# kegtroller_v1.net
KiCad netlist of a schematic drawn in EAGLE
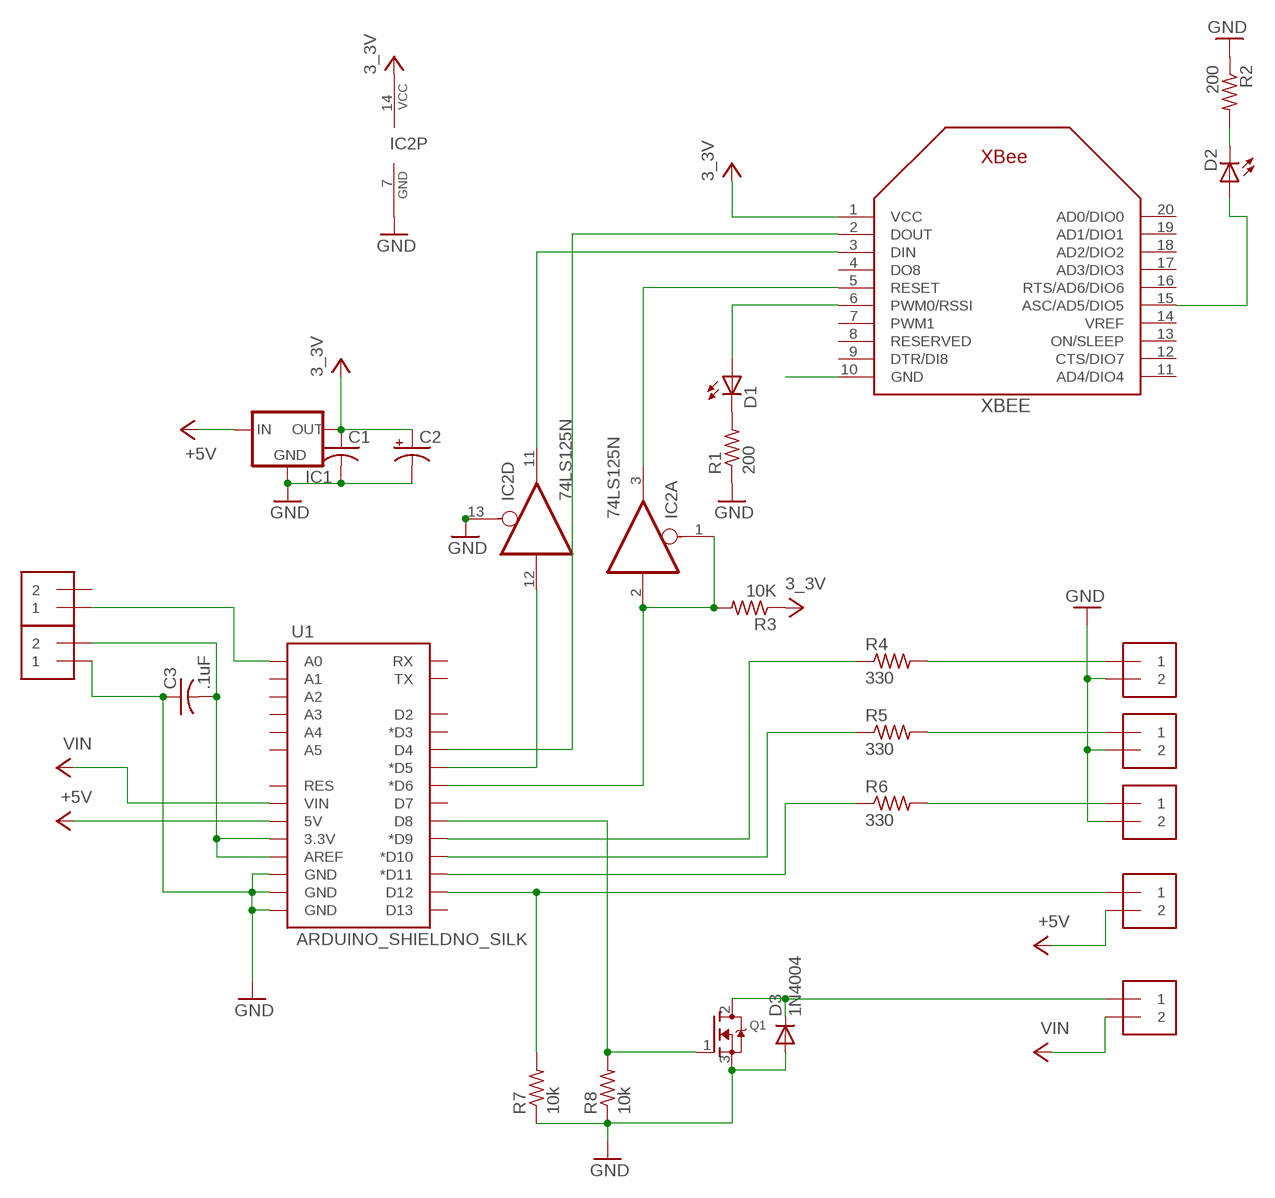
[diagram p0: schematic, sheet 1]

(export (version "E")
  (design (tool "Eeschema 10.0.6"))
  (components
    (comp (ref "C1")
      (value "C-US025-025X050")
      (footprint "eagle-import:C025-025X050")
      (libsource (lib "eagle-import") (part "rcl-ez_C-US025-025X050"))
    )
    (comp (ref "C2")
      (value "CPOL-USE2.5-5")
      (footprint "eagle-import:E2,5-5")
      (libsource (lib "eagle-import") (part "CPOL-USE2.5-5"))
    )
    (comp (ref "C3")
      (value ".1uF")
      (footprint "eagle-import:C025-025X050")
      (libsource (lib "eagle-import") (part "C-US025-025X050"))
    )
    (comp (ref "D1")
      (value "LED3MM")
      (footprint "eagle-import:LED3MM")
      (libsource (lib "eagle-import") (part "LED3MM"))
    )
    (comp (ref "D2")
      (value "LED3MM")
      (footprint "eagle-import:LED3MM")
      (libsource (lib "eagle-import") (part "LED3MM"))
    )
    (comp (ref "D3")
      (value "1N4004")
      (footprint "eagle-import:DO41-10")
      (libsource (lib "eagle-import") (part "1N4004"))
    )
    (comp (ref "IC1")
      (value "MC1700")
      (footprint "eagle-import:TO92")
      (libsource (lib "eagle-import") (part "MC1700"))
    )
    (comp (ref "IC2")
      (value "74LS125N")
      (footprint "eagle-import:DIL14")
      (libsource (lib "eagle-import") (part "74125NLS"))
    )
    (comp (ref "J1")
      (value "1X2-3.5MM")
      (footprint "eagle-import:1X2-3.5MM")
      (libsource (lib "eagle-import") (part "1X2-3.5MM"))
    )
    (comp (ref "J2")
      (value "1X2-3.5MM")
      (footprint "eagle-import:1X2-3.5MM")
      (libsource (lib "eagle-import") (part "1X2-3.5MM"))
    )
    (comp (ref "J3")
      (value "1X2-3.5MM")
      (footprint "eagle-import:1X2-3.5MM")
      (libsource (lib "eagle-import") (part "1X2-3.5MM"))
    )
    (comp (ref "J4")
      (value "1X2-3.5MM")
      (footprint "eagle-import:1X2-3.5MM")
      (libsource (lib "eagle-import") (part "1X2-3.5MM"))
    )
    (comp (ref "J5")
      (value "1X2-3.5MM")
      (footprint "eagle-import:1X2-3.5MM")
      (libsource (lib "eagle-import") (part "1X2-3.5MM"))
    )
    (comp (ref "J6")
      (value "1X2-3.5MM")
      (footprint "eagle-import:1X2-3.5MM")
      (libsource (lib "eagle-import") (part "1X2-3.5MM"))
    )
    (comp (ref "J7")
      (value "1X2-3.5MM")
      (footprint "eagle-import:1X2-3.5MM")
      (libsource (lib "eagle-import") (part "1X2-3.5MM"))
    )
    (comp (ref "Q1")
      (value "MOSFET-NGDS_TO220V")
      (footprint "eagle-import:TO220V")
      (libsource (lib "eagle-import") (part "MOSFET-NGDS_TO220V"))
    )
    (comp (ref "R1")
      (value "200")
      (footprint "eagle-import:0207_10")
      (libsource (lib "eagle-import") (part "rcl-ez_R-US_0207/10"))
    )
    (comp (ref "R2")
      (value "200")
      (footprint "eagle-import:0207_10")
      (libsource (lib "eagle-import") (part "rcl-ez_R-US_0207/10"))
    )
    (comp (ref "R3")
      (value "10K")
      (footprint "eagle-import:0207_10")
      (libsource (lib "eagle-import") (part "rcl-ez_R-US_0207/10"))
    )
    (comp (ref "R4")
      (value "330")
      (footprint "eagle-import:0204_5")
      (libsource (lib "eagle-import") (part "R-US_0204/5"))
    )
    (comp (ref "R5")
      (value "330")
      (footprint "eagle-import:0204_5")
      (libsource (lib "eagle-import") (part "R-US_0204/5"))
    )
    (comp (ref "R6")
      (value "330")
      (footprint "eagle-import:0204_5")
      (libsource (lib "eagle-import") (part "R-US_0204/5"))
    )
    (comp (ref "R7")
      (value "10k")
      (footprint "eagle-import:0204_5")
      (libsource (lib "eagle-import") (part "R-US_0204/5"))
    )
    (comp (ref "R8")
      (value "10k")
      (footprint "eagle-import:0204_5")
      (libsource (lib "eagle-import") (part "R-US_0204/5"))
    )
    (comp (ref "U1")
      (value "ARDUINO_SHIELDNO_SILK")
      (footprint "eagle-import:DUEMILANOVE_VIAS")
      (libsource (lib "eagle-import") (part "ARDUINO_SHIELDNO_SILK"))
    )
    (comp (ref "XBEE")
      (value "XBEE")
      (footprint "eagle-import:XBEE")
      (libsource (lib "eagle-import") (part "XBEE"))
    )
  )
  (nets
    (net (code "1") (name "+5V") (class "Default")
      (node (ref "IC1") (pin "2") (pinfunction "IN_2") (pintype "input"))
      (node (ref "J4") (pin "2") (pinfunction "2_2") (pintype "passive"))
      (node (ref "U1") (pin "5V") (pinfunction "5V_5V") (pintype "bidirectional"))
    )
    (net (code "2") (name "3_3V") (class "Default")
      (node (ref "C1") (pin "1") (pinfunction "1_1") (pintype "passive"))
      (node (ref "C2") (pin "+") (pinfunction "+_+") (pintype "passive"))
      (node (ref "IC1") (pin "3") (pinfunction "OUT_3") (pintype "passive"))
      (node (ref "IC2") (pin "14") (pinfunction "VCC_14") (pintype "power_in"))
      (node (ref "R3") (pin "1") (pinfunction "1_1") (pintype "passive"))
      (node (ref "XBEE") (pin "1") (pinfunction "VCC_1") (pintype "power_in"))
    )
    (net (code "3") (name "GND") (class "Default")
      (node (ref "C1") (pin "2") (pinfunction "2_2") (pintype "passive"))
      (node (ref "C2") (pin "-") (pinfunction "-_-") (pintype "passive"))
      (node (ref "C3") (pin "1") (pinfunction "1_1") (pintype "passive"))
      (node (ref "D3") (pin "A") (pinfunction "A_A") (pintype "passive"))
      (node (ref "IC1") (pin "1") (pinfunction "GND_1") (pintype "input"))
      (node (ref "IC2") (pin "13") (pinfunction "OE_13") (pintype "input"))
      (node (ref "IC2") (pin "7") (pinfunction "GND_7") (pintype "power_in"))
      (node (ref "J1") (pin "2") (pinfunction "2_2") (pintype "passive"))
      (node (ref "J2") (pin "2") (pinfunction "2_2") (pintype "passive"))
      (node (ref "J3") (pin "2") (pinfunction "2_2") (pintype "passive"))
      (node (ref "J6") (pin "1") (pinfunction "1_1") (pintype "passive"))
      (node (ref "Q1") (pin "3") (pinfunction "S_3") (pintype "bidirectional"))
      (node (ref "R1") (pin "1") (pinfunction "1_1") (pintype "passive"))
      (node (ref "R2") (pin "1") (pinfunction "1_1") (pintype "passive"))
      (node (ref "R7") (pin "1") (pinfunction "1_1") (pintype "passive"))
      (node (ref "R8") (pin "1") (pinfunction "1_1") (pintype "passive"))
      (node (ref "U1") (pin "GND@0") (pinfunction "GND_GND@0") (pintype "bidirectional"))
      (node (ref "U1") (pin "GND@1") (pinfunction "GND_GND@1") (pintype "bidirectional"))
      (node (ref "U1") (pin "GND@2") (pinfunction "GND_GND@2") (pintype "bidirectional"))
      (node (ref "XBEE") (pin "10") (pinfunction "GND_10") (pintype "power_in"))
    )
    (net (code "4") (name "Net-(C3-Pad2)") (class "Default")
      (node (ref "C3") (pin "2") (pinfunction "2_2") (pintype "passive"))
      (node (ref "J6") (pin "2") (pinfunction "2_2") (pintype "passive"))
      (node (ref "U1") (pin "3.3V") (pinfunction "3.3V_3.3V") (pintype "bidirectional"))
      (node (ref "U1") (pin "AREF") (pinfunction "AREF_AREF") (pintype "bidirectional"))
    )
    (net (code "5") (name "Net-(D1-C)") (class "Default")
      (node (ref "D1") (pin "K") (pinfunction "C_K") (pintype "passive"))
      (node (ref "R1") (pin "2") (pinfunction "2_2") (pintype "passive"))
    )
    (net (code "6") (name "Net-(D2-C)") (class "Default")
      (node (ref "D2") (pin "K") (pinfunction "C_K") (pintype "passive"))
      (node (ref "R2") (pin "2") (pinfunction "2_2") (pintype "passive"))
    )
    (net (code "7") (name "Net-(IC2A-I)") (class "Default")
      (node (ref "IC2") (pin "1") (pinfunction "OE_1") (pintype "input"))
      (node (ref "IC2") (pin "2") (pinfunction "I_2") (pintype "input"))
      (node (ref "R3") (pin "2") (pinfunction "2_2") (pintype "passive"))
      (node (ref "U1") (pin "D6") (pinfunction "*D6_D6") (pintype "bidirectional"))
    )
    (net (code "8") (name "Net-(IC2A-O)") (class "Default")
      (node (ref "IC2") (pin "3") (pinfunction "O_3") (pintype "tri_state"))
      (node (ref "XBEE") (pin "5") (pinfunction "RESET_5") (pintype "input"))
    )
    (net (code "9") (name "Net-(IC2D-I)") (class "Default")
      (node (ref "IC2") (pin "12") (pinfunction "I_12") (pintype "input"))
      (node (ref "U1") (pin "D5") (pinfunction "*D5_D5") (pintype "bidirectional"))
    )
    (net (code "10") (name "Net-(IC2D-O)") (class "Default")
      (node (ref "IC2") (pin "11") (pinfunction "O_11") (pintype "tri_state"))
      (node (ref "XBEE") (pin "3") (pinfunction "DIN_3") (pintype "input"))
    )
    (net (code "11") (name "Net-(J1-Pad1)") (class "Default")
      (node (ref "J1") (pin "1") (pinfunction "1_1") (pintype "passive"))
      (node (ref "R4") (pin "2") (pinfunction "2_2") (pintype "passive"))
    )
    (net (code "12") (name "Net-(J2-Pad1)") (class "Default")
      (node (ref "J2") (pin "1") (pinfunction "1_1") (pintype "passive"))
      (node (ref "R5") (pin "2") (pinfunction "2_2") (pintype "passive"))
    )
    (net (code "13") (name "Net-(J3-Pad1)") (class "Default")
      (node (ref "J3") (pin "1") (pinfunction "1_1") (pintype "passive"))
      (node (ref "R6") (pin "2") (pinfunction "2_2") (pintype "passive"))
    )
    (net (code "14") (name "Net-(J4-Pad1)") (class "Default")
      (node (ref "J4") (pin "1") (pinfunction "1_1") (pintype "passive"))
      (node (ref "R7") (pin "2") (pinfunction "2_2") (pintype "passive"))
      (node (ref "U1") (pin "D12") (pinfunction "D12_D12") (pintype "bidirectional"))
    )
    (net (code "15") (name "Net-(J5-Pad1)") (class "Default")
      (node (ref "J5") (pin "1") (pinfunction "1_1") (pintype "passive"))
      (node (ref "U1") (pin "A0") (pinfunction "A0_A0") (pintype "bidirectional"))
    )
    (net (code "16") (name "Net-(Q1-D)") (class "Default")
      (node (ref "D3") (pin "C") (pinfunction "C_C") (pintype "passive"))
      (node (ref "J7") (pin "1") (pinfunction "1_1") (pintype "passive"))
      (node (ref "Q1") (pin "2") (pinfunction "D_2") (pintype "bidirectional"))
    )
    (net (code "17") (name "Net-(Q1-G)") (class "Default")
      (node (ref "Q1") (pin "1") (pinfunction "G_1") (pintype "bidirectional"))
      (node (ref "R8") (pin "2") (pinfunction "2_2") (pintype "passive"))
      (node (ref "U1") (pin "D8") (pinfunction "D8_D8") (pintype "bidirectional"))
    )
    (net (code "18") (name "Net-(U1-*D9)") (class "Default")
      (node (ref "R4") (pin "1") (pinfunction "1_1") (pintype "passive"))
      (node (ref "U1") (pin "D9") (pinfunction "*D9_D9") (pintype "bidirectional"))
    )
    (net (code "19") (name "Net-(U1-*D10)") (class "Default")
      (node (ref "R5") (pin "1") (pinfunction "1_1") (pintype "passive"))
      (node (ref "U1") (pin "D10") (pinfunction "*D10_D10") (pintype "bidirectional"))
    )
    (net (code "20") (name "Net-(U1-*D11)") (class "Default")
      (node (ref "R6") (pin "1") (pinfunction "1_1") (pintype "passive"))
      (node (ref "U1") (pin "D11") (pinfunction "*D11_D11") (pintype "bidirectional"))
    )
    (net (code "21") (name "Net-(XBEE-ASC{slash}AD5{slash}DIO5)") (class "Default")
      (node (ref "D2") (pin "A") (pinfunction "A_A") (pintype "passive"))
      (node (ref "XBEE") (pin "15") (pinfunction "ASC/AD5/DIO5_15") (pintype "bidirectional"))
    )
    (net (code "22") (name "Net-(XBEE-DOUT)") (class "Default")
      (node (ref "U1") (pin "D4") (pinfunction "D4_D4") (pintype "bidirectional"))
      (node (ref "XBEE") (pin "2") (pinfunction "DOUT_2") (pintype "output"))
    )
    (net (code "23") (name "Net-(XBEE-PWM0{slash}RSSI)") (class "Default")
      (node (ref "D1") (pin "A") (pinfunction "A_A") (pintype "passive"))
      (node (ref "XBEE") (pin "6") (pinfunction "PWM0/RSSI_6") (pintype "output"))
    )
    (net (code "24") (name "VIN") (class "Default")
      (node (ref "J7") (pin "2") (pinfunction "2_2") (pintype "passive"))
      (node (ref "U1") (pin "VIN") (pinfunction "VIN_VIN") (pintype "bidirectional"))
    )
    (net (code "25") (name "unconnected-(J5-Pad2)") (class "Default")
      (node (ref "J5") (pin "2") (pinfunction "2_2") (pintype "passive"))
    )
    (net (code "26") (name "unconnected-(U1-*D3-PadD3)") (class "Default")
      (node (ref "U1") (pin "D3") (pinfunction "*D3_D3") (pintype "bidirectional"))
    )
    (net (code "27") (name "unconnected-(U1-PadA1)") (class "Default")
      (node (ref "U1") (pin "A1") (pinfunction "A1_A1") (pintype "bidirectional"))
    )
    (net (code "28") (name "unconnected-(U1-PadA2)") (class "Default")
      (node (ref "U1") (pin "A2") (pinfunction "A2_A2") (pintype "bidirectional"))
    )
    (net (code "29") (name "unconnected-(U1-PadA3)") (class "Default")
      (node (ref "U1") (pin "A3") (pinfunction "A3_A3") (pintype "bidirectional"))
    )
    (net (code "30") (name "unconnected-(U1-PadA4)") (class "Default")
      (node (ref "U1") (pin "A4") (pinfunction "A4_A4") (pintype "bidirectional"))
    )
    (net (code "31") (name "unconnected-(U1-PadA5)") (class "Default")
      (node (ref "U1") (pin "A5") (pinfunction "A5_A5") (pintype "bidirectional"))
    )
    (net (code "32") (name "unconnected-(U1-PadD2)") (class "Default")
      (node (ref "U1") (pin "D2") (pinfunction "D2_D2") (pintype "bidirectional"))
    )
    (net (code "33") (name "unconnected-(U1-PadD7)") (class "Default")
      (node (ref "U1") (pin "D7") (pinfunction "D7_D7") (pintype "bidirectional"))
    )
    (net (code "34") (name "unconnected-(U1-PadD13)") (class "Default")
      (node (ref "U1") (pin "D13") (pinfunction "D13_D13") (pintype "bidirectional"))
    )
    (net (code "35") (name "unconnected-(U1-PadRES)") (class "Default")
      (node (ref "U1") (pin "RES") (pinfunction "RES_RES") (pintype "bidirectional"))
    )
    (net (code "36") (name "unconnected-(U1-PadRX)") (class "Default")
      (node (ref "U1") (pin "RX") (pinfunction "RX_RX") (pintype "bidirectional"))
    )
    (net (code "37") (name "unconnected-(U1-PadTX)") (class "Default")
      (node (ref "U1") (pin "TX") (pinfunction "TX_TX") (pintype "bidirectional"))
    )
    (net (code "38") (name "unconnected-(XBEE-AD0{slash}DIO0-Pad20)") (class "Default")
      (node (ref "XBEE") (pin "20") (pinfunction "AD0/DIO0_20") (pintype "bidirectional"))
    )
    (net (code "39") (name "unconnected-(XBEE-AD1{slash}DIO1-Pad19)") (class "Default")
      (node (ref "XBEE") (pin "19") (pinfunction "AD1/DIO1_19") (pintype "bidirectional"))
    )
    (net (code "40") (name "unconnected-(XBEE-AD2{slash}DIO2-Pad18)") (class "Default")
      (node (ref "XBEE") (pin "18") (pinfunction "AD2/DIO2_18") (pintype "bidirectional"))
    )
    (net (code "41") (name "unconnected-(XBEE-AD3{slash}DIO3-Pad17)") (class "Default")
      (node (ref "XBEE") (pin "17") (pinfunction "AD3/DIO3_17") (pintype "bidirectional"))
    )
    (net (code "42") (name "unconnected-(XBEE-AD4{slash}DIO4-Pad11)") (class "Default")
      (node (ref "XBEE") (pin "11") (pinfunction "AD4/DIO4_11") (pintype "bidirectional"))
    )
    (net (code "43") (name "unconnected-(XBEE-CTS{slash}DIO7-Pad12)") (class "Default")
      (node (ref "XBEE") (pin "12") (pinfunction "CTS/DIO7_12") (pintype "bidirectional"))
    )
    (net (code "44") (name "unconnected-(XBEE-DO8-Pad4)") (class "Default")
      (node (ref "XBEE") (pin "4") (pinfunction "DO8_4") (pintype "output"))
    )
    (net (code "45") (name "unconnected-(XBEE-DTR{slash}DI8-Pad9)") (class "Default")
      (node (ref "XBEE") (pin "9") (pinfunction "DTR/DI8_9") (pintype "input"))
    )
    (net (code "46") (name "unconnected-(XBEE-ON{slash}SLEEP-Pad13)") (class "Default")
      (node (ref "XBEE") (pin "13") (pinfunction "ON/SLEEP_13") (pintype "output"))
    )
    (net (code "47") (name "unconnected-(XBEE-PWM1-Pad7)") (class "Default")
      (node (ref "XBEE") (pin "7") (pinfunction "PWM1_7") (pintype "output"))
    )
    (net (code "48") (name "unconnected-(XBEE-RESERVED-Pad8)") (class "Default")
      (node (ref "XBEE") (pin "8") (pinfunction "RESERVED_8") (pintype "no_connect"))
    )
    (net (code "49") (name "unconnected-(XBEE-RTS{slash}AD6{slash}DIO6-Pad16)") (class "Default")
      (node (ref "XBEE") (pin "16") (pinfunction "RTS/AD6/DIO6_16") (pintype "bidirectional"))
    )
    (net (code "50") (name "unconnected-(XBEE-VREF-Pad14)") (class "Default")
      (node (ref "XBEE") (pin "14") (pinfunction "VREF_14") (pintype "input"))
    )
  )
)
